# board.net
KiCad netlist of a schematic drawn in EAGLE
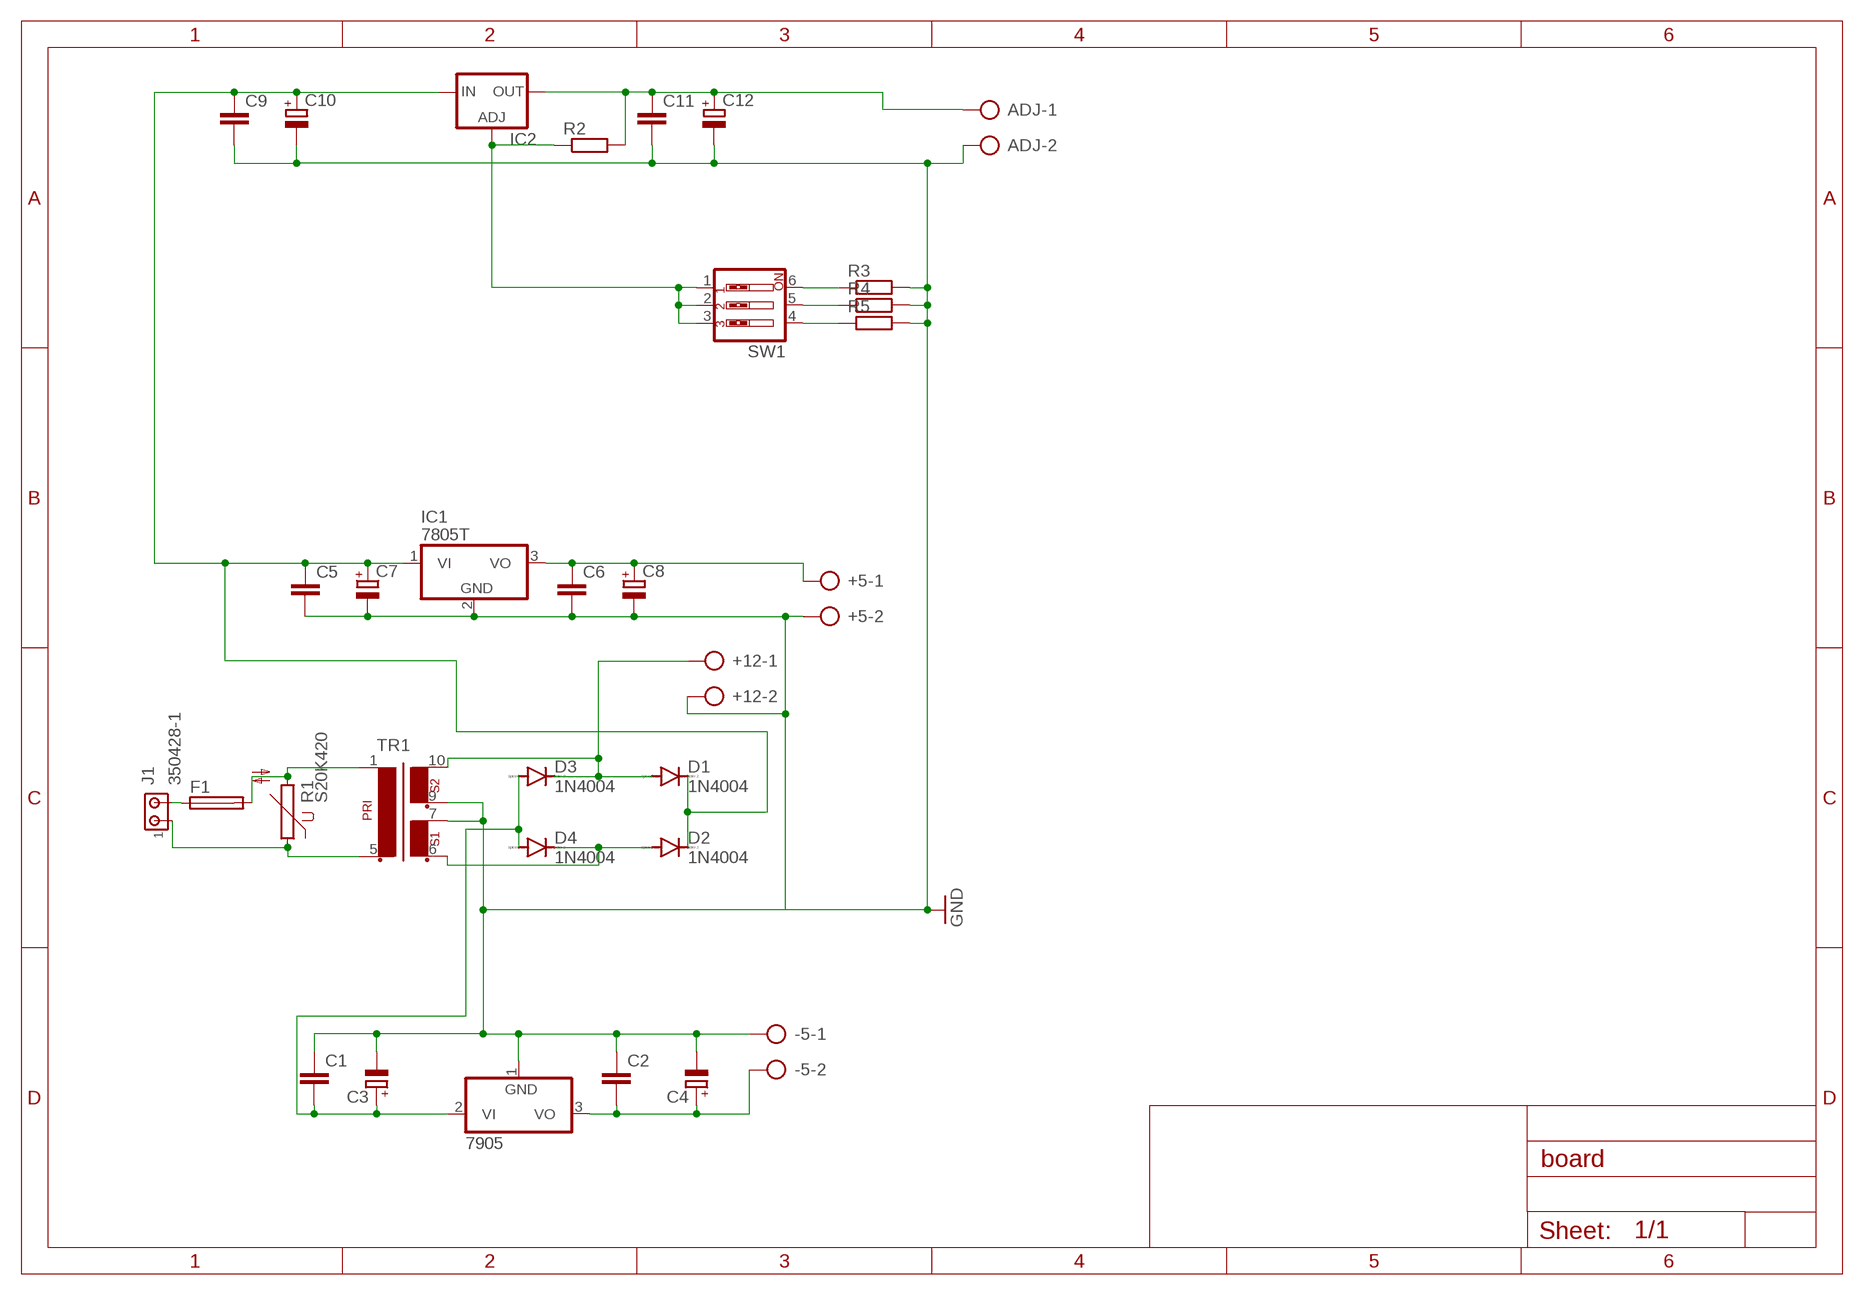
[diagram p0: schematic, sheet 1]

(export (version "E")
  (design (tool "Eeschema 10.0.6"))
  (components
    (comp (ref "+5")
      (value "AK500/2-H")
      (footprint "eagle-import:AK500_2-H")
      (libsource (lib "eagle-import") (part "AK500/2-H"))
    )
    (comp (ref "+12")
      (value "AK500/2-H")
      (footprint "eagle-import:AK500_2-H")
      (libsource (lib "eagle-import") (part "AK500/2-H"))
    )
    (comp (ref "-5")
      (value "AK500/2-H")
      (footprint "eagle-import:AK500_2-H")
      (libsource (lib "eagle-import") (part "AK500/2-H"))
    )
    (comp (ref "7905")
      (value "7905T")
      (footprint "eagle-import:TO220H")
      (libsource (lib "eagle-import") (part "79T05"))
    )
    (comp (ref "ADJ")
      (value "AK500/2-H")
      (footprint "eagle-import:AK500_2-H")
      (libsource (lib "eagle-import") (part "AK500/2-H"))
    )
    (comp (ref "C1")
      (value "C-EU025-025X050")
      (footprint "eagle-import:C025-025X050")
      (libsource (lib "eagle-import") (part "C-EU025-025X050"))
    )
    (comp (ref "C2")
      (value "C-EU025-025X050")
      (footprint "eagle-import:C025-025X050")
      (libsource (lib "eagle-import") (part "C-EU025-025X050"))
    )
    (comp (ref "C3")
      (value "CPOL-EUE2,5-6E")
      (footprint "eagle-import:E2,5-6E")
      (libsource (lib "eagle-import") (part "CPOL-EUE2,5-6E"))
    )
    (comp (ref "C4")
      (value "CPOL-EUE2,5-6E")
      (footprint "eagle-import:E2,5-6E")
      (libsource (lib "eagle-import") (part "CPOL-EUE2,5-6E"))
    )
    (comp (ref "C5")
      (value "C-EU025-025X050")
      (footprint "eagle-import:C025-025X050")
      (libsource (lib "eagle-import") (part "C-EU025-025X050"))
    )
    (comp (ref "C6")
      (value "C-EU025-025X050")
      (footprint "eagle-import:C025-025X050")
      (libsource (lib "eagle-import") (part "C-EU025-025X050"))
    )
    (comp (ref "C7")
      (value "CPOL-EUE2,5-6E")
      (footprint "eagle-import:E2,5-6E")
      (libsource (lib "eagle-import") (part "CPOL-EUE2,5-6E"))
    )
    (comp (ref "C8")
      (value "CPOL-EUE2,5-6E")
      (footprint "eagle-import:E2,5-6E")
      (libsource (lib "eagle-import") (part "CPOL-EUE2,5-6E"))
    )
    (comp (ref "C9")
      (value "C-EU025-025X050")
      (footprint "eagle-import:C025-025X050")
      (libsource (lib "eagle-import") (part "C-EU025-025X050"))
    )
    (comp (ref "C10")
      (value "CPOL-EUE2,5-6E")
      (footprint "eagle-import:E2,5-6E")
      (libsource (lib "eagle-import") (part "CPOL-EUE2,5-6E"))
    )
    (comp (ref "C11")
      (value "C-EU025-025X050")
      (footprint "eagle-import:C025-025X050")
      (libsource (lib "eagle-import") (part "C-EU025-025X050"))
    )
    (comp (ref "C12")
      (value "CPOL-EUE2,5-6E")
      (footprint "eagle-import:E2,5-6E")
      (libsource (lib "eagle-import") (part "CPOL-EUE2,5-6E"))
    )
    (comp (ref "D1")
      (value "1N4004")
      (footprint "eagle-import:DO41-10")
      (libsource (lib "eagle-import") (part "1N4004"))
    )
    (comp (ref "D2")
      (value "1N4004")
      (footprint "eagle-import:DO41-10")
      (libsource (lib "eagle-import") (part "1N4004"))
    )
    (comp (ref "D3")
      (value "1N4004")
      (footprint "eagle-import:DO41-10")
      (libsource (lib "eagle-import") (part "1N4004"))
    )
    (comp (ref "D4")
      (value "1N4004")
      (footprint "eagle-import:DO41-10")
      (libsource (lib "eagle-import") (part "1N4004"))
    )
    (comp (ref "F1")
      (value "GSH15")
      (footprint "eagle-import:GSH15")
      (fields (field (name "MPN") "64900001039"))
      (libsource (lib "eagle-import") (part "GSH15"))
    )
    (comp (ref "IC1")
      (value "7805T")
      (footprint "eagle-import:TO220H")
      (libsource (lib "eagle-import") (part "78T05"))
    )
    (comp (ref "IC2")
      (value "LM317TL")
      (footprint "eagle-import:317TL")
      (libsource (lib "eagle-import") (part "LM317TL"))
    )
    (comp (ref "J1")
      (value "350428-1")
      (footprint "eagle-import:350428-1")
      (libsource (lib "eagle-import") (part "350428-1"))
    )
    (comp (ref "R1")
      (value "S20K420")
      (footprint "eagle-import:S20K420")
      (libsource (lib "eagle-import") (part "S20K420"))
    )
    (comp (ref "R2")
      (value "R-EU_0204/7")
      (footprint "eagle-import:0204_7")
      (libsource (lib "eagle-import") (part "R-EU_0204/7"))
    )
    (comp (ref "R3")
      (value "R-EU_0204/7")
      (footprint "eagle-import:0204_7")
      (libsource (lib "eagle-import") (part "R-EU_0204/7"))
    )
    (comp (ref "R4")
      (value "R-EU_0204/7")
      (footprint "eagle-import:0204_7")
      (libsource (lib "eagle-import") (part "R-EU_0204/7"))
    )
    (comp (ref "R5")
      (value "R-EU_0204/7")
      (footprint "eagle-import:0204_7")
      (libsource (lib "eagle-import") (part "R-EU_0204/7"))
    )
    (comp (ref "SW1")
      (value "SW_DIP-3")
      (footprint "eagle-import:EDG-03")
      (libsource (lib "eagle-import") (part "SW_DIP-3"))
    )
    (comp (ref "TR1")
      (value "EI30-2")
      (footprint "eagle-import:EI30-2")
      (libsource (lib "eagle-import") (part "EI30-2"))
    )
  )
  (nets
    (net (code "1") (name "GND") (class "Default")
      (node (ref "+12") (pin "2") (pinfunction "KL_2") (pintype "passive"))
      (node (ref "+5") (pin "2") (pinfunction "KL_2") (pintype "passive"))
      (node (ref "-5") (pin "1") (pinfunction "KL_1") (pintype "passive"))
      (node (ref "7905") (pin "1") (pinfunction "GND_1") (pintype "passive"))
      (node (ref "ADJ") (pin "2") (pinfunction "KL_2") (pintype "passive"))
      (node (ref "C1") (pin "1") (pinfunction "1_1") (pintype "passive"))
      (node (ref "C10") (pin "-") (pinfunction "-_-") (pintype "passive"))
      (node (ref "C11") (pin "2") (pinfunction "2_2") (pintype "passive"))
      (node (ref "C12") (pin "-") (pinfunction "-_-") (pintype "passive"))
      (node (ref "C2") (pin "1") (pinfunction "1_1") (pintype "passive"))
      (node (ref "C3") (pin "-") (pinfunction "-_-") (pintype "passive"))
      (node (ref "C4") (pin "-") (pinfunction "-_-") (pintype "passive"))
      (node (ref "C5") (pin "2") (pinfunction "2_2") (pintype "passive"))
      (node (ref "C6") (pin "2") (pinfunction "2_2") (pintype "passive"))
      (node (ref "C7") (pin "-") (pinfunction "-_-") (pintype "passive"))
      (node (ref "C8") (pin "-") (pinfunction "-_-") (pintype "passive"))
      (node (ref "C9") (pin "2") (pinfunction "2_2") (pintype "passive"))
      (node (ref "IC1") (pin "2") (pinfunction "GND_2") (pintype "passive"))
      (node (ref "R3") (pin "2") (pinfunction "2_2") (pintype "passive"))
      (node (ref "R4") (pin "2") (pinfunction "2_2") (pintype "passive"))
      (node (ref "R5") (pin "2") (pinfunction "2_2") (pintype "passive"))
      (node (ref "TR1") (pin "7") (pinfunction "4_7") (pintype "passive"))
      (node (ref "TR1") (pin "9") (pinfunction "5_9") (pintype "passive"))
    )
    (net (code "2") (name "Net-(+5A-KL)") (class "Default")
      (node (ref "+5") (pin "1") (pinfunction "KL_1") (pintype "passive"))
      (node (ref "C6") (pin "1") (pinfunction "1_1") (pintype "passive"))
      (node (ref "C8") (pin "+") (pinfunction "+_+") (pintype "passive"))
      (node (ref "IC1") (pin "3") (pinfunction "VO_3") (pintype "passive"))
    )
    (net (code "3") (name "Net-(+12A-KL)") (class "Default")
      (node (ref "+12") (pin "1") (pinfunction "KL_1") (pintype "passive"))
      (node (ref "D1") (pin "A") (pinfunction "A_A") (pintype "passive"))
      (node (ref "D3") (pin "C") (pinfunction "C_C") (pintype "passive"))
      (node (ref "TR1") (pin "10") (pinfunction "6_10") (pintype "passive"))
    )
    (net (code "4") (name "Net-(-5B-KL)") (class "Default")
      (node (ref "-5") (pin "2") (pinfunction "KL_2") (pintype "passive"))
      (node (ref "7905") (pin "3") (pinfunction "VO_3") (pintype "passive"))
      (node (ref "C2") (pin "2") (pinfunction "2_2") (pintype "passive"))
      (node (ref "C4") (pin "+") (pinfunction "+_+") (pintype "passive"))
    )
    (net (code "5") (name "Net-(7905-VI)") (class "Default")
      (node (ref "7905") (pin "2") (pinfunction "VI_2") (pintype "input"))
      (node (ref "C1") (pin "2") (pinfunction "2_2") (pintype "passive"))
      (node (ref "C3") (pin "+") (pinfunction "+_+") (pintype "passive"))
      (node (ref "D3") (pin "A") (pinfunction "A_A") (pintype "passive"))
      (node (ref "D4") (pin "A") (pinfunction "A_A") (pintype "passive"))
    )
    (net (code "6") (name "Net-(ADJA-KL)") (class "Default")
      (node (ref "ADJ") (pin "1") (pinfunction "KL_1") (pintype "passive"))
      (node (ref "C11") (pin "1") (pinfunction "1_1") (pintype "passive"))
      (node (ref "C12") (pin "+") (pinfunction "+_+") (pintype "passive"))
      (node (ref "IC2") (pin "2") (pinfunction "OUT_2") (pintype "passive"))
      (node (ref "R2") (pin "2") (pinfunction "2_2") (pintype "passive"))
    )
    (net (code "7") (name "Net-(F1-Pad1)") (class "Default")
      (node (ref "F1") (pin "1") (pinfunction "1_1") (pintype "passive"))
      (node (ref "J1") (pin "2") (pinfunction "2_2") (pintype "passive"))
    )
    (net (code "8") (name "Net-(F1-Pad2)") (class "Default")
      (node (ref "F1") (pin "2") (pinfunction "2_2") (pintype "passive"))
      (node (ref "R1") (pin "2") (pinfunction "2_2") (pintype "passive"))
      (node (ref "TR1") (pin "1") (pinfunction "1_1") (pintype "passive"))
    )
    (net (code "9") (name "Net-(IC1-VI)") (class "Default")
      (node (ref "C10") (pin "+") (pinfunction "+_+") (pintype "passive"))
      (node (ref "C5") (pin "1") (pinfunction "1_1") (pintype "passive"))
      (node (ref "C7") (pin "+") (pinfunction "+_+") (pintype "passive"))
      (node (ref "C9") (pin "1") (pinfunction "1_1") (pintype "passive"))
      (node (ref "D1") (pin "C") (pinfunction "C_C") (pintype "passive"))
      (node (ref "D2") (pin "C") (pinfunction "C_C") (pintype "passive"))
      (node (ref "IC1") (pin "1") (pinfunction "VI_1") (pintype "input"))
      (node (ref "IC2") (pin "3") (pinfunction "IN_3") (pintype "input"))
    )
    (net (code "10") (name "Net-(IC2-ADJ)") (class "Default")
      (node (ref "IC2") (pin "1") (pinfunction "ADJ_1") (pintype "input"))
      (node (ref "R2") (pin "1") (pinfunction "1_1") (pintype "passive"))
      (node (ref "SW1") (pin "1") (pinfunction "1_1") (pintype "passive"))
      (node (ref "SW1") (pin "2") (pinfunction "2_2") (pintype "passive"))
      (node (ref "SW1") (pin "3") (pinfunction "3_3") (pintype "passive"))
    )
    (net (code "11") (name "Net-(R3-Pad1)") (class "Default")
      (node (ref "R3") (pin "1") (pinfunction "1_1") (pintype "passive"))
      (node (ref "SW1") (pin "6") (pinfunction "6_6") (pintype "passive"))
    )
    (net (code "12") (name "Net-(R4-Pad1)") (class "Default")
      (node (ref "R4") (pin "1") (pinfunction "1_1") (pintype "passive"))
      (node (ref "SW1") (pin "5") (pinfunction "5_5") (pintype "passive"))
    )
    (net (code "13") (name "Net-(R5-Pad1)") (class "Default")
      (node (ref "R5") (pin "1") (pinfunction "1_1") (pintype "passive"))
      (node (ref "SW1") (pin "4") (pinfunction "4_4") (pintype "passive"))
    )
    (net (code "14") (name "Net-(TR1-2)") (class "Default")
      (node (ref "J1") (pin "1") (pinfunction "1_1") (pintype "passive"))
      (node (ref "R1") (pin "1") (pinfunction "1_1") (pintype "passive"))
      (node (ref "TR1") (pin "5") (pinfunction "2_5") (pintype "passive"))
    )
    (net (code "15") (name "Net-(TR1-3)") (class "Default")
      (node (ref "D2") (pin "A") (pinfunction "A_A") (pintype "passive"))
      (node (ref "D4") (pin "C") (pinfunction "C_C") (pintype "passive"))
      (node (ref "TR1") (pin "6") (pinfunction "3_6") (pintype "passive"))
    )
  )
)
